# esp32_receiver.net
KiCad netlist of a schematic drawn in EasyEDA
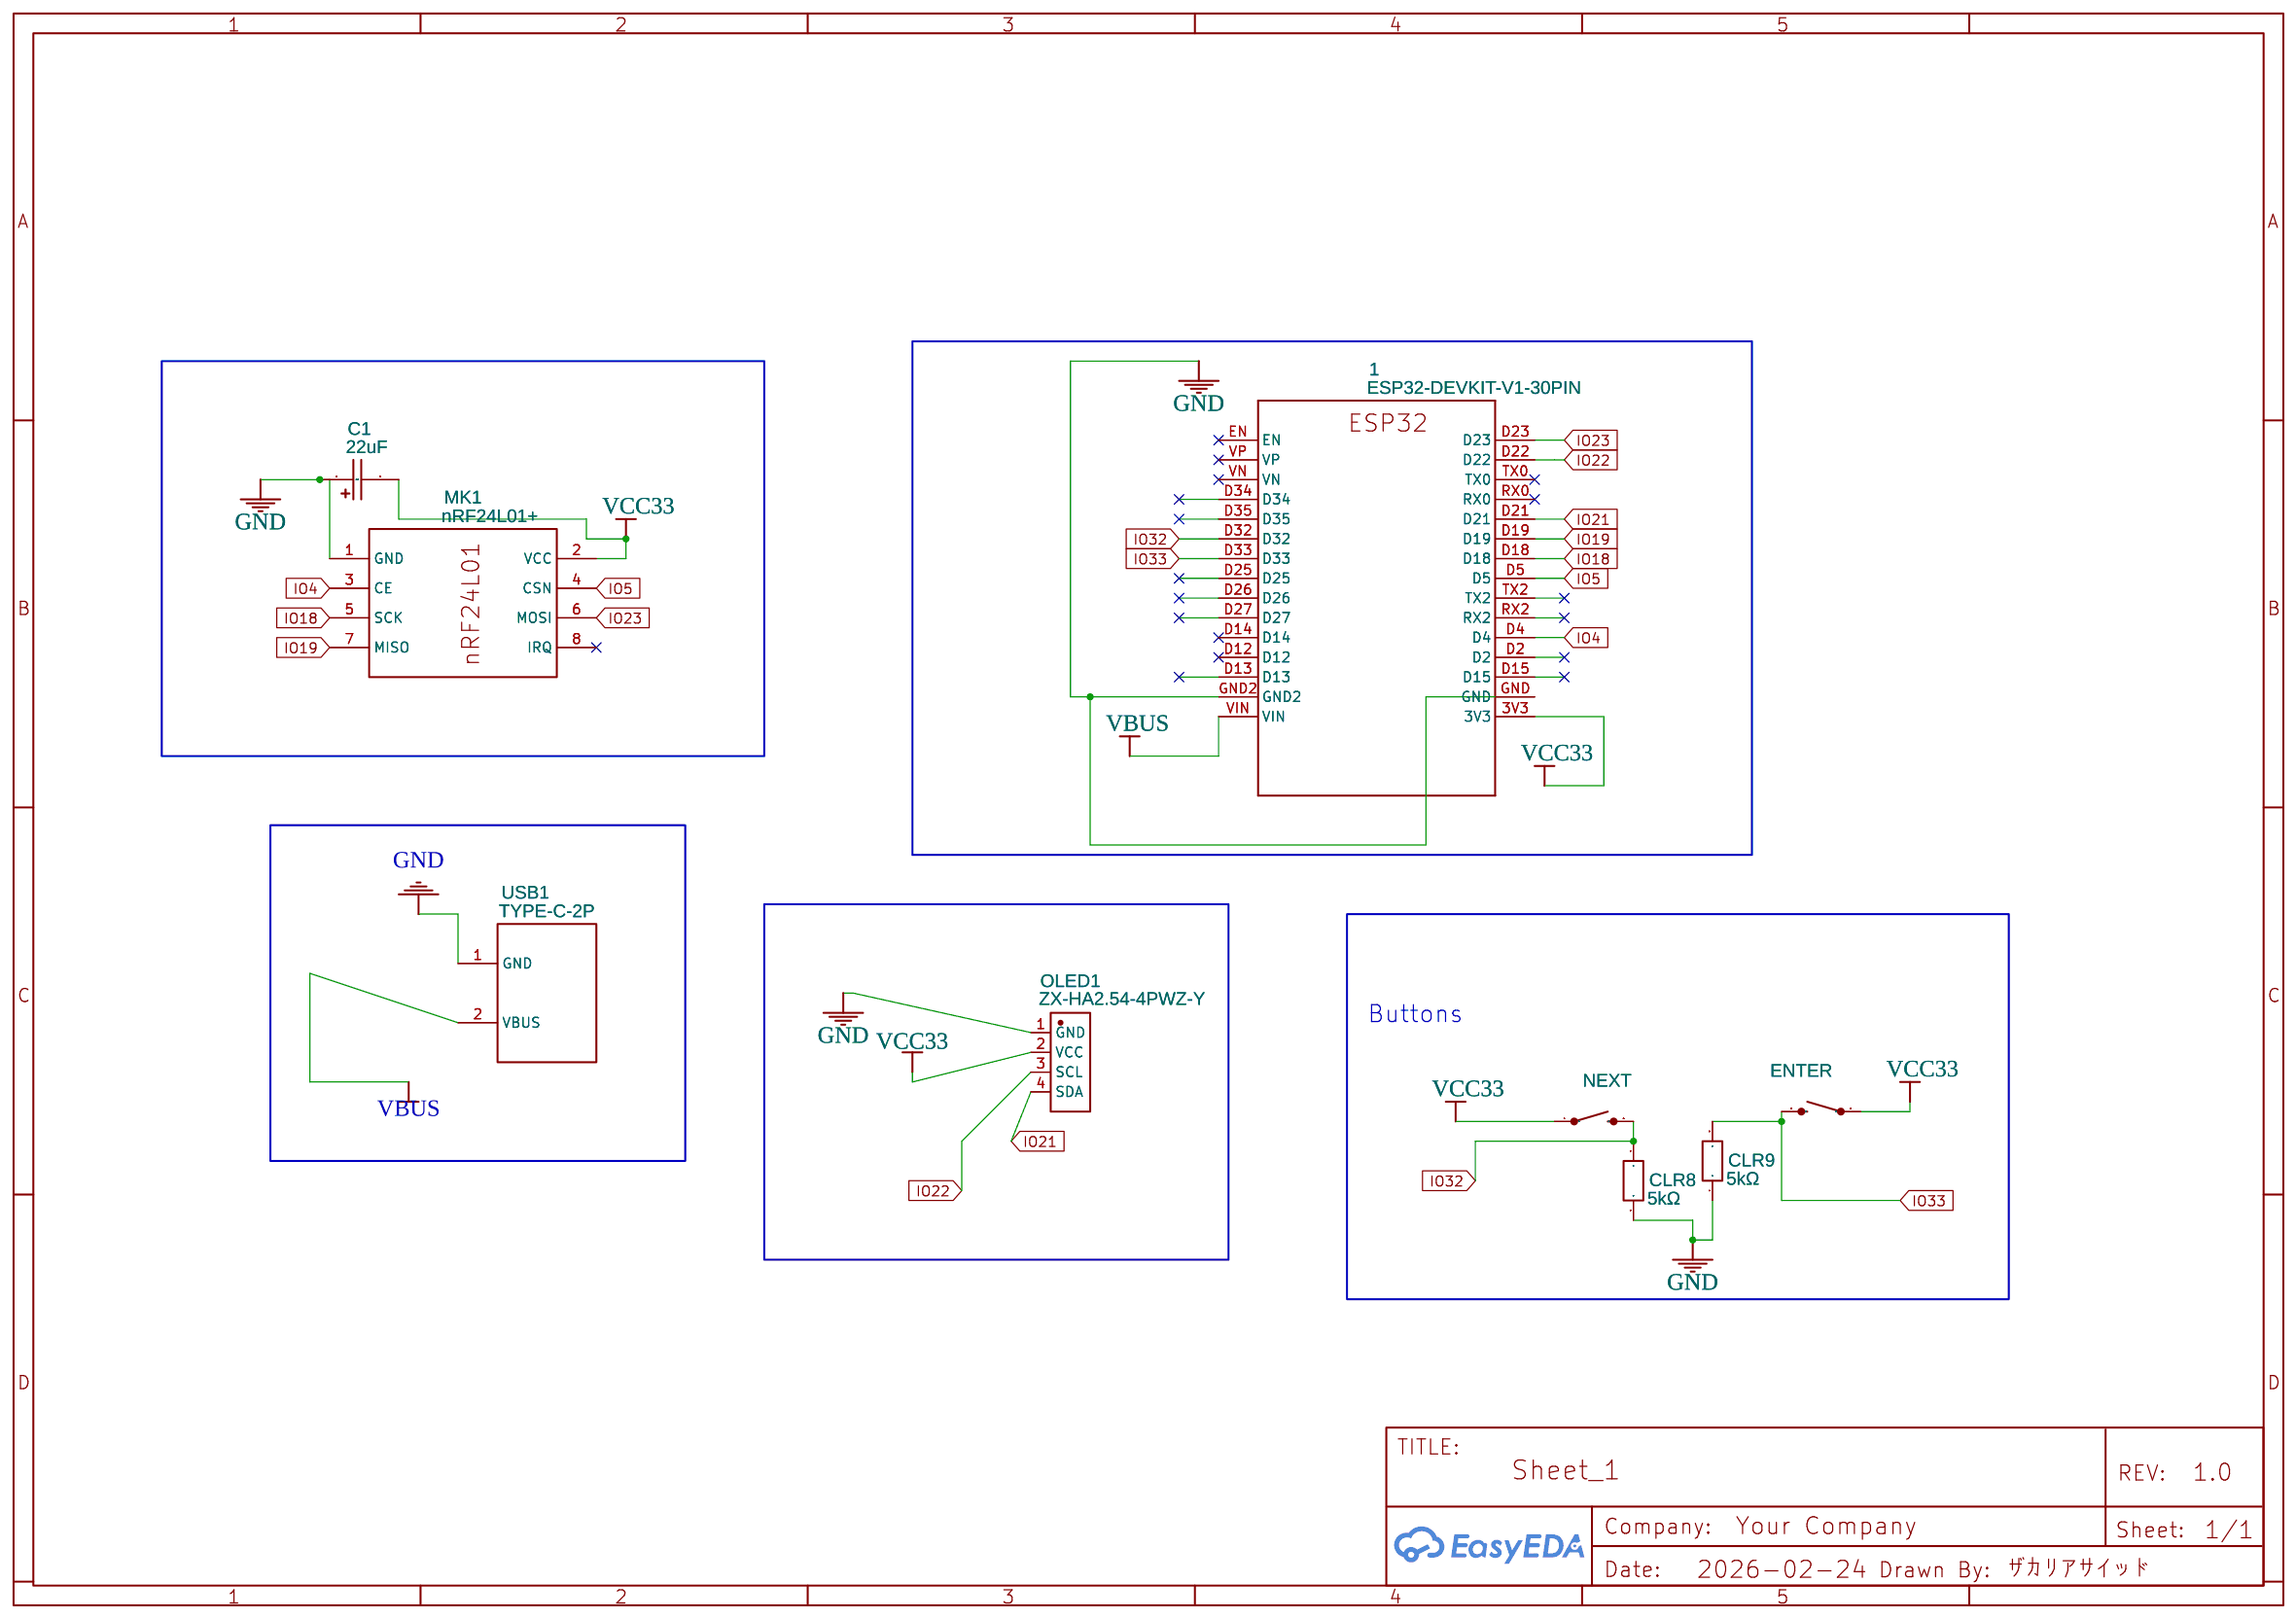
[diagram p0: schematic sheet]

(export (version "E")
  (design (tool "Eeschema 10.0.6"))
  (components
    (comp (ref "1") (value "ESP32-DEVKIT-V1-30PIN") (libsource (lib "") (part "ESP32-DEVKIT-V1-30PIN")))
    (comp (ref "C1")
      (value "22uF")
      (fields (field (name "Manufacturer Part") "UES1V220MPM1TD") (field (name "Manufacturer") "Nichicon"))
      (libsource (lib "") (part "22uF_16V"))
    )
    (comp (ref "CLR8") (value "5kΩ") (libsource (lib "") (part "R_AXIAL-0.4_EU")))
    (comp (ref "CLR9") (value "5kΩ") (libsource (lib "") (part "R_AXIAL-0.4_EU_1")))
    (comp (ref "ENTER") (value "SWITCHES_PTH_EZ") (libsource (lib "") (part "SWITCHES_PTH_EZ_1")))
    (comp (ref "MK1") (value "nRF24L01+") (libsource (lib "") (part "nRF24L01+")))
    (comp (ref "NEXT") (value "SWITCHES_PTH_EZ") (libsource (lib "") (part "SWITCHES_PTH_EZ")))
    (comp (ref "OLED1")
      (value "ZX-HA2.54-4PWZ-Y")
      (fields (field (name "Manufacturer") "Megastar(兆星)"))
      (libsource (lib "") (part "ZX-HA2.54-4PWZ-Y"))
    )
    (comp (ref "USB1") (value "TYPE-C-2P") (libsource (lib "") (part "TYPE-C-2P")))
  )
  (nets
    (net (code "1") (name "GND") (class "Default")
      (node (ref "1") (pin "GND") (pinfunction "GND_GND") (pintype "unspecified"))
      (node (ref "1") (pin "GND2") (pinfunction "GND2_GND2") (pintype "unspecified"))
      (node (ref "C1") (pin "1") (pinfunction "1_1") (pintype "unspecified"))
      (node (ref "CLR8") (pin "2") (pinfunction "2_2") (pintype "unspecified"))
      (node (ref "CLR9") (pin "1") (pinfunction "1_1") (pintype "unspecified"))
      (node (ref "MK1") (pin "1") (pinfunction "GND_1") (pintype "unspecified"))
      (node (ref "OLED1") (pin "1") (pinfunction "GND_1") (pintype "unspecified"))
      (node (ref "USB1") (pin "1") (pinfunction "GND_1") (pintype "unspecified"))
    )
    (net (code "2") (name "IO4") (class "Default")
      (node (ref "1") (pin "D4") (pinfunction "D4_D4") (pintype "unspecified"))
      (node (ref "MK1") (pin "3") (pinfunction "CE_3") (pintype "unspecified"))
    )
    (net (code "3") (name "IO5") (class "Default")
      (node (ref "1") (pin "D5") (pinfunction "D5_D5") (pintype "unspecified"))
      (node (ref "MK1") (pin "4") (pinfunction "CSN_4") (pintype "unspecified"))
    )
    (net (code "4") (name "IO18") (class "Default")
      (node (ref "1") (pin "D18") (pinfunction "D18_D18") (pintype "unspecified"))
      (node (ref "MK1") (pin "5") (pinfunction "SCK_5") (pintype "unspecified"))
    )
    (net (code "5") (name "IO19") (class "Default")
      (node (ref "1") (pin "D19") (pinfunction "D19_D19") (pintype "unspecified"))
      (node (ref "MK1") (pin "7") (pinfunction "MISO_7") (pintype "unspecified"))
    )
    (net (code "6") (name "IO21") (class "Default")
      (node (ref "1") (pin "D21") (pinfunction "D21_D21") (pintype "unspecified"))
      (node (ref "OLED1") (pin "4") (pinfunction "SDA_4") (pintype "unspecified"))
    )
    (net (code "7") (name "IO22") (class "Default")
      (node (ref "1") (pin "D22") (pinfunction "D22_D22") (pintype "unspecified"))
      (node (ref "OLED1") (pin "3") (pinfunction "SCL_3") (pintype "unspecified"))
    )
    (net (code "8") (name "IO23") (class "Default")
      (node (ref "1") (pin "D23") (pinfunction "D23_D23") (pintype "unspecified"))
      (node (ref "MK1") (pin "6") (pinfunction "MOSI_6") (pintype "unspecified"))
    )
    (net (code "9") (name "IO32") (class "Default")
      (node (ref "1") (pin "D32") (pinfunction "D32_D32") (pintype "unspecified"))
      (node (ref "CLR8") (pin "1") (pinfunction "1_1") (pintype "unspecified"))
      (node (ref "NEXT") (pin "3") (pinfunction "2_3") (pintype "unspecified"))
    )
    (net (code "10") (name "IO33") (class "Default")
      (node (ref "1") (pin "D33") (pinfunction "D33_D33") (pintype "unspecified"))
      (node (ref "CLR9") (pin "2") (pinfunction "2_2") (pintype "unspecified"))
      (node (ref "ENTER") (pin "3") (pinfunction "2_3") (pintype "unspecified"))
    )
    (net (code "11") (name "VBUS") (class "Default")
      (node (ref "1") (pin "VIN") (pinfunction "VIN_VIN") (pintype "unspecified"))
      (node (ref "USB1") (pin "2") (pinfunction "VBUS_2") (pintype "unspecified"))
    )
    (net (code "12") (name "VCC33") (class "Default")
      (node (ref "1") (pin "3V3") (pinfunction "3V3_3V3") (pintype "unspecified"))
      (node (ref "C1") (pin "2") (pinfunction "2_2") (pintype "unspecified"))
      (node (ref "ENTER") (pin "1") (pinfunction "1_1") (pintype "unspecified"))
      (node (ref "MK1") (pin "2") (pinfunction "VCC_2") (pintype "unspecified"))
      (node (ref "NEXT") (pin "1") (pinfunction "1_1") (pintype "unspecified"))
      (node (ref "OLED1") (pin "2") (pinfunction "VCC_2") (pintype "unspecified"))
    )
    (net (code "13") (name "unconnected-(1-PadD2)") (class "Default")
      (node (ref "1") (pin "D2") (pinfunction "D2_D2") (pintype "unspecified+no_connect"))
    )
    (net (code "14") (name "unconnected-(1-PadD12)") (class "Default")
      (node (ref "1") (pin "D12") (pinfunction "D12_D12") (pintype "unspecified+no_connect"))
    )
    (net (code "15") (name "unconnected-(1-PadD13)") (class "Default")
      (node (ref "1") (pin "D13") (pinfunction "D13_D13") (pintype "unspecified+no_connect"))
    )
    (net (code "16") (name "unconnected-(1-PadD14)") (class "Default")
      (node (ref "1") (pin "D14") (pinfunction "D14_D14") (pintype "unspecified+no_connect"))
    )
    (net (code "17") (name "unconnected-(1-PadD15)") (class "Default")
      (node (ref "1") (pin "D15") (pinfunction "D15_D15") (pintype "unspecified+no_connect"))
    )
    (net (code "18") (name "unconnected-(1-PadD25)") (class "Default")
      (node (ref "1") (pin "D25") (pinfunction "D25_D25") (pintype "unspecified+no_connect"))
    )
    (net (code "19") (name "unconnected-(1-PadD26)") (class "Default")
      (node (ref "1") (pin "D26") (pinfunction "D26_D26") (pintype "unspecified+no_connect"))
    )
    (net (code "20") (name "unconnected-(1-PadD27)") (class "Default")
      (node (ref "1") (pin "D27") (pinfunction "D27_D27") (pintype "unspecified+no_connect"))
    )
    (net (code "21") (name "unconnected-(1-PadD34)") (class "Default")
      (node (ref "1") (pin "D34") (pinfunction "D34_D34") (pintype "unspecified+no_connect"))
    )
    (net (code "22") (name "unconnected-(1-PadD35)") (class "Default")
      (node (ref "1") (pin "D35") (pinfunction "D35_D35") (pintype "unspecified+no_connect"))
    )
    (net (code "23") (name "unconnected-(1-PadEN)") (class "Default")
      (node (ref "1") (pin "EN") (pinfunction "EN_EN") (pintype "unspecified+no_connect"))
    )
    (net (code "24") (name "unconnected-(1-PadRX0)") (class "Default")
      (node (ref "1") (pin "RX0") (pinfunction "RX0_RX0") (pintype "unspecified+no_connect"))
    )
    (net (code "25") (name "unconnected-(1-PadRX2)") (class "Default")
      (node (ref "1") (pin "RX2") (pinfunction "RX2_RX2") (pintype "unspecified+no_connect"))
    )
    (net (code "26") (name "unconnected-(1-PadTX0)") (class "Default")
      (node (ref "1") (pin "TX0") (pinfunction "TX0_TX0") (pintype "unspecified+no_connect"))
    )
    (net (code "27") (name "unconnected-(1-PadTX2)") (class "Default")
      (node (ref "1") (pin "TX2") (pinfunction "TX2_TX2") (pintype "unspecified+no_connect"))
    )
    (net (code "28") (name "unconnected-(1-PadVN)") (class "Default")
      (node (ref "1") (pin "VN") (pinfunction "VN_VN") (pintype "unspecified+no_connect"))
    )
    (net (code "29") (name "unconnected-(1-PadVP)") (class "Default")
      (node (ref "1") (pin "VP") (pinfunction "VP_VP") (pintype "unspecified+no_connect"))
    )
    (net (code "30") (name "unconnected-(MK1-IRQ-Pad8)") (class "Default")
      (node (ref "MK1") (pin "8") (pinfunction "IRQ_8") (pintype "unspecified+no_connect"))
    )
  )
)
